# Mother_board_slot.net
KiCad netlist of a schematic drawn in Altium Designer
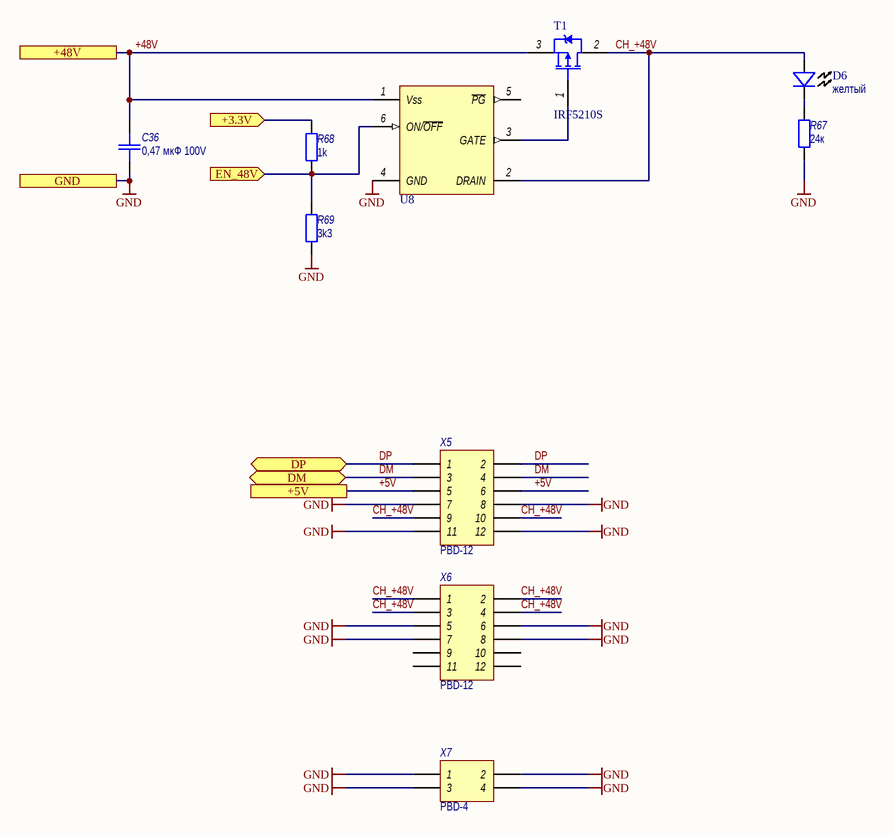
[diagram p0: Mother_board_slot.SchDoc]

(export (version "E")
  (design (tool "Eeschema 10.0.6"))
  (components
    (comp (ref "C36")
      (value "0,47 мкФ 100V")
      (footprint "SMD_0805")
      (description "Capacitor")
      (libsource (lib "*") (part "Capacitor"))
    )
    (comp (ref "D6")
      (value "желтый")
      (footprint "LED-0805")
      (fields (field (name "Comment") "LED"))
      (libsource (lib "Diod") (part "LED"))
    )
    (comp (ref "R67")
      (value "24к")
      (footprint "SMD_0805")
      (description "Resistor")
      (libsource (lib "Passive") (part "Resistor"))
    )
    (comp (ref "R68")
      (value "1k")
      (footprint "SMD_0805")
      (description "Resistor")
      (libsource (lib "") (part "Resistor_1"))
    )
    (comp (ref "R69")
      (value "3k3")
      (footprint "SMD_0805")
      (description "Resistor")
      (libsource (lib "Passive") (part "Resistor"))
    )
    (comp (ref "T1")
      (value "IRF5210S")
      (footprint "D2Pak")
      (description "P channel Power MosFET")
      (libsource (lib "IRF5210S") (part "IRF5210S"))
    )
    (comp (ref "U8")
      (value "MAX5902")
      (footprint "SOT23-6")
      (description "Hot-swap controller")
      (fields (field (name "PUBLISHER") "Altium Limited"))
      (libsource (lib "MAX5902") (part "MAX5902"))
    )
    (comp (ref "X5")
      (value "Header 2X12")
      (footprint "PBD-12")
      (description "Header, 12-Pin, Dual row")
      (fields (field (name "НАИМЕНОВАНИЕ") "PBD-12"))
      (libsource (lib "Connector") (part "Header 2X12"))
    )
    (comp (ref "X6")
      (value "Header 2X12")
      (footprint "PBD-12")
      (description "Header, 12-Pin, Dual row")
      (fields (field (name "НАИМЕНОВАНИЕ") "PBD-12"))
      (libsource (lib "Connector") (part "Header 2X12"))
    )
    (comp (ref "X7")
      (value "Header 2X4")
      (footprint "PBD-4")
      (description "Header, 4-Pin, Dual row")
      (fields (field (name "НАИМЕНОВАНИЕ") "PBD-4"))
      (libsource (lib "Connector") (part "Header 2X4"))
    )
  )
  (nets
    (net (code "1") (name "/+3.3V") (class "Default")
      (node (ref "R68") (pin "1") (pinfunction "1_1") (pintype "passive"))
    )
    (net (code "2") (name "/+5V") (class "Default")
      (node (ref "X5") (pin "5") (pinfunction "5_5") (pintype "passive"))
      (node (ref "X5") (pin "6") (pinfunction "6_6") (pintype "passive"))
    )
    (net (code "3") (name "/+48V") (class "Default")
      (node (ref "C36") (pin "2") (pinfunction "2_2") (pintype "passive"))
      (node (ref "T1") (pin "3") (pinfunction "S_3") (pintype "passive"))
      (node (ref "U8") (pin "1") (pinfunction "Vss_1") (pintype "power_in"))
    )
    (net (code "4") (name "/CH_+48V") (class "Default")
      (node (ref "D6") (pin "1") (pinfunction "A_1") (pintype "passive"))
      (node (ref "T1") (pin "2") (pinfunction "D_2") (pintype "passive"))
      (node (ref "U8") (pin "2") (pinfunction "DRAIN_2") (pintype "passive"))
      (node (ref "X5") (pin "10") (pinfunction "10_10") (pintype "passive"))
      (node (ref "X5") (pin "9") (pinfunction "9_9") (pintype "passive"))
      (node (ref "X6") (pin "1") (pinfunction "1_1") (pintype "passive"))
      (node (ref "X6") (pin "2") (pinfunction "2_2") (pintype "passive"))
      (node (ref "X6") (pin "3") (pinfunction "3_3") (pintype "passive"))
      (node (ref "X6") (pin "4") (pinfunction "4_4") (pintype "passive"))
    )
    (net (code "5") (name "/DM") (class "Default")
      (node (ref "X5") (pin "3") (pinfunction "3_3") (pintype "passive"))
      (node (ref "X5") (pin "4") (pinfunction "4_4") (pintype "passive"))
    )
    (net (code "6") (name "/DP") (class "Default")
      (node (ref "X5") (pin "1") (pinfunction "1_1") (pintype "passive"))
      (node (ref "X5") (pin "2") (pinfunction "2_2") (pintype "passive"))
    )
    (net (code "7") (name "/EN_48V") (class "Default")
      (node (ref "R68") (pin "2") (pinfunction "2_2") (pintype "passive"))
      (node (ref "R69") (pin "2") (pinfunction "2_2") (pintype "passive"))
      (node (ref "U8") (pin "6") (pinfunction "ON/~{OFF}_6") (pintype "input"))
    )
    (net (code "8") (name "GND") (class "Default")
      (node (ref "C36") (pin "1") (pinfunction "1_1") (pintype "passive"))
      (node (ref "R67") (pin "1") (pinfunction "1_1") (pintype "passive"))
      (node (ref "R69") (pin "1") (pinfunction "1_1") (pintype "passive"))
      (node (ref "U8") (pin "4") (pinfunction "GND_4") (pintype "power_in"))
      (node (ref "X5") (pin "11") (pinfunction "11_11") (pintype "passive"))
      (node (ref "X5") (pin "12") (pinfunction "12_12") (pintype "passive"))
      (node (ref "X5") (pin "7") (pinfunction "7_7") (pintype "passive"))
      (node (ref "X5") (pin "8") (pinfunction "8_8") (pintype "passive"))
      (node (ref "X6") (pin "5") (pinfunction "5_5") (pintype "passive"))
      (node (ref "X6") (pin "6") (pinfunction "6_6") (pintype "passive"))
      (node (ref "X6") (pin "7") (pinfunction "7_7") (pintype "passive"))
      (node (ref "X6") (pin "8") (pinfunction "8_8") (pintype "passive"))
      (node (ref "X7") (pin "1") (pinfunction "1_1") (pintype "passive"))
      (node (ref "X7") (pin "2") (pinfunction "2_2") (pintype "passive"))
      (node (ref "X7") (pin "3") (pinfunction "3_3") (pintype "passive"))
      (node (ref "X7") (pin "4") (pinfunction "4_4") (pintype "passive"))
    )
    (net (code "9") (name "Net-(D6-K)") (class "Default")
      (node (ref "D6") (pin "2") (pinfunction "K_2") (pintype "passive"))
      (node (ref "R67") (pin "2") (pinfunction "2_2") (pintype "passive"))
    )
    (net (code "10") (name "Net-(T1-G)") (class "Default")
      (node (ref "T1") (pin "1") (pinfunction "G_1") (pintype "passive"))
      (node (ref "U8") (pin "3") (pinfunction "GATE_3") (pintype "output"))
    )
    (net (code "11") (name "unconnected-(U8-~{PG}-Pad5)") (class "Default")
      (node (ref "U8") (pin "5") (pinfunction "~{PG}_5") (pintype "output"))
    )
    (net (code "12") (name "unconnected-(X6-Pad9)") (class "Default")
      (node (ref "X6") (pin "9") (pinfunction "9_9") (pintype "passive"))
    )
    (net (code "13") (name "unconnected-(X6-Pad10)") (class "Default")
      (node (ref "X6") (pin "10") (pinfunction "10_10") (pintype "passive"))
    )
    (net (code "14") (name "unconnected-(X6-Pad11)") (class "Default")
      (node (ref "X6") (pin "11") (pinfunction "11_11") (pintype "passive"))
    )
    (net (code "15") (name "unconnected-(X6-Pad12)") (class "Default")
      (node (ref "X6") (pin "12") (pinfunction "12_12") (pintype "passive"))
    )
  )
)
